# pj7.net
KiCad netlist of a schematic drawn in EAGLE
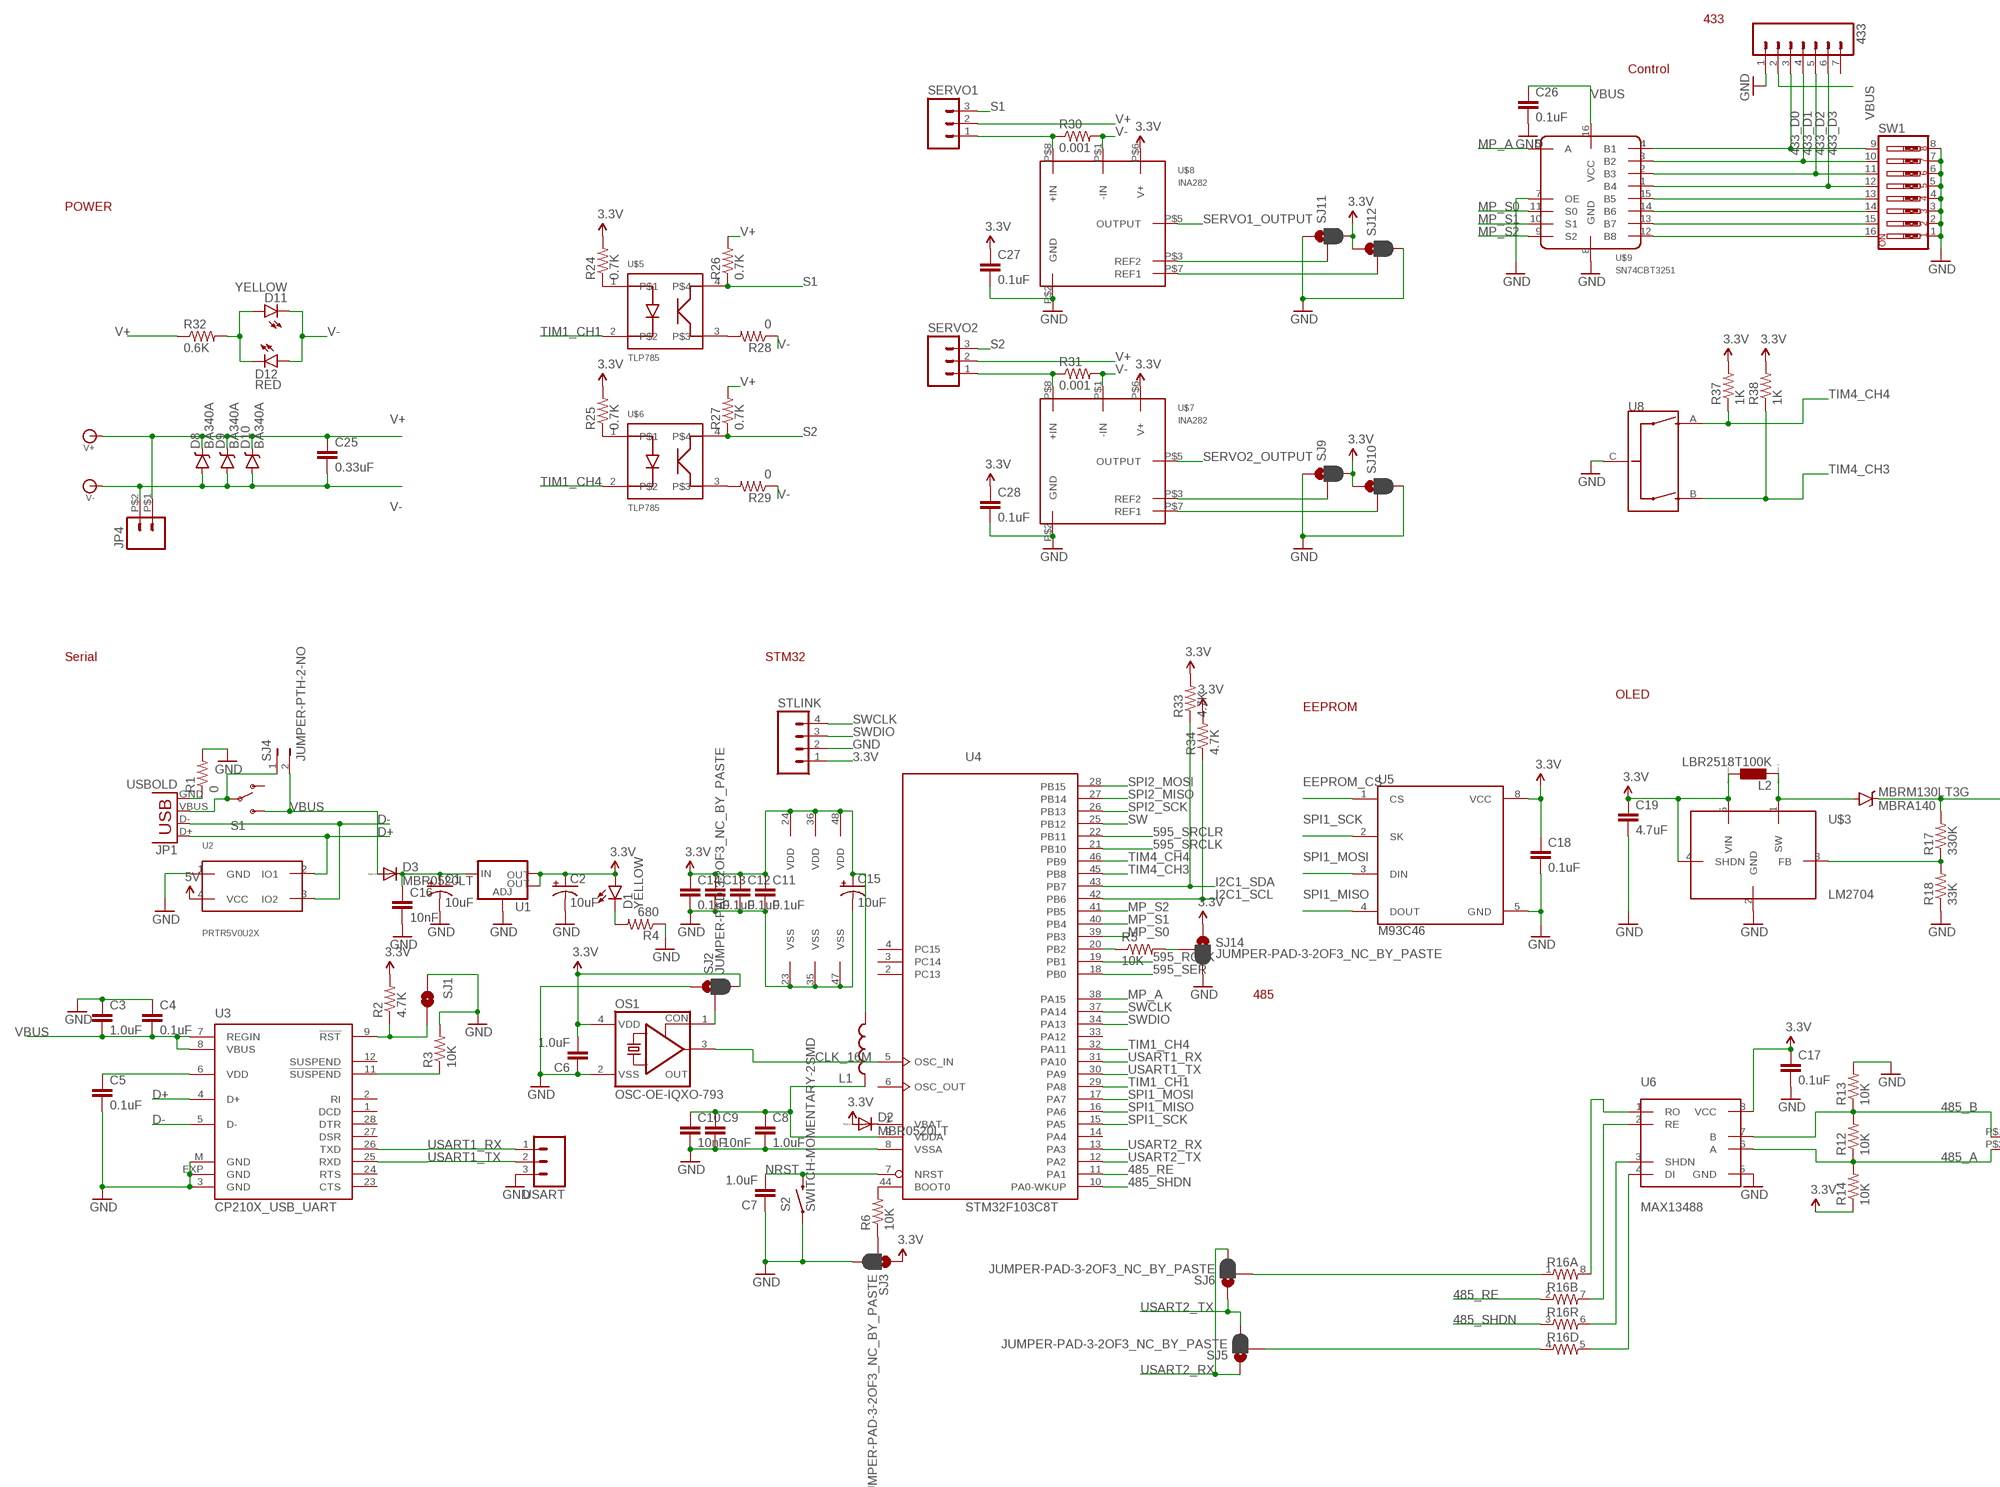
[diagram p0: schematic, sheet 1, part 1 of 2]
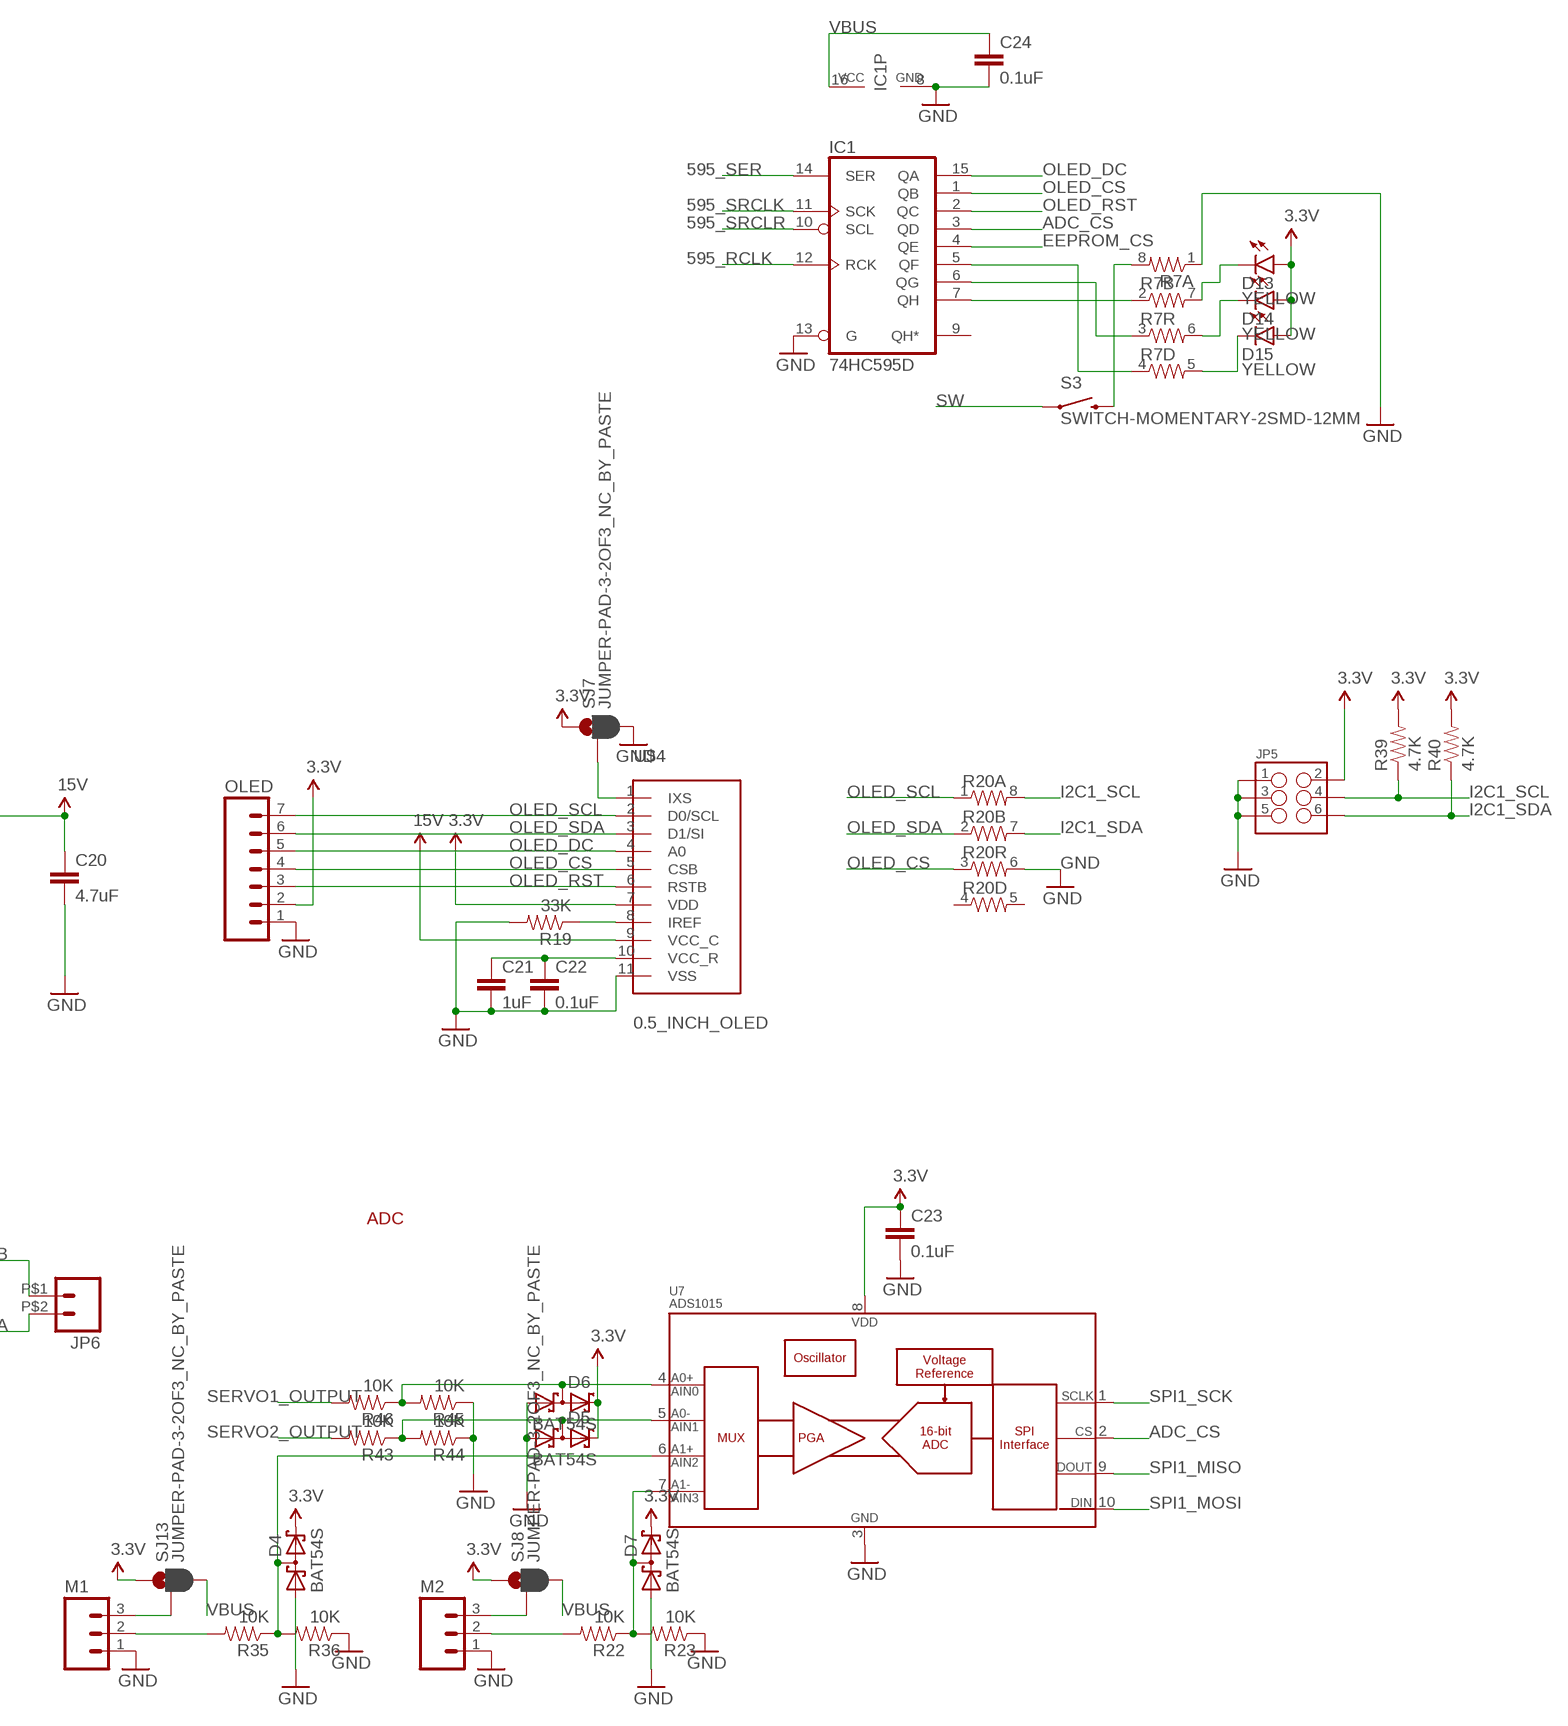
[diagram p1: schematic, sheet 1, part 2 of 2]

(export (version "E")
  (design (tool "Eeschema 10.0.6"))
  (components
    (comp (ref "433")
      (value "M07LOCK")
      (footprint "eagle-import:1X07_LOCK")
      (libsource (lib "eagle-import") (part "M07LOCK"))
    )
    (comp (ref "C1")
      (value "10uF")
      (footprint "eagle-import:EIA3216")
      (libsource (lib "eagle-import") (part "10UF-16V-10%(TANT)"))
    )
    (comp (ref "C2")
      (value "10uF")
      (footprint "eagle-import:EIA3216")
      (libsource (lib "eagle-import") (part "10UF-16V-10%(TANT)"))
    )
    (comp (ref "C3")
      (value "1.0uF")
      (footprint "eagle-import:0603-CAP")
      (libsource (lib "eagle-import") (part "1.0UF-16V-10%(0603)"))
    )
    (comp (ref "C4")
      (value "0.1uF")
      (footprint "eagle-import:0603-CAP")
      (libsource (lib "eagle-import") (part "0.1UF-25V-5%(0603)"))
    )
    (comp (ref "C5")
      (value "0.1uF")
      (footprint "eagle-import:0603-CAP")
      (libsource (lib "eagle-import") (part "0.1UF-25V-5%(0603)"))
    )
    (comp (ref "C6")
      (value "1.0uF")
      (footprint "eagle-import:0603-CAP")
      (libsource (lib "eagle-import") (part "1.0UF-16V-10%(0603)"))
    )
    (comp (ref "C7")
      (value "1.0uF")
      (footprint "eagle-import:0603-CAP")
      (libsource (lib "eagle-import") (part "1.0UF-16V-10%(0603)"))
    )
    (comp (ref "C8")
      (value "1.0uF")
      (footprint "eagle-import:0603-CAP")
      (libsource (lib "eagle-import") (part "1.0UF-16V-10%(0603)"))
    )
    (comp (ref "C9")
      (value "10nF")
      (footprint "eagle-import:0603-CAP")
      (libsource (lib "eagle-import") (part "10NF/10000PF-50V-10%(0603)"))
    )
    (comp (ref "C10")
      (value "10nF")
      (footprint "eagle-import:0603-CAP")
      (libsource (lib "eagle-import") (part "10NF/10000PF-50V-10%(0603)"))
    )
    (comp (ref "C11")
      (value "0.1uF")
      (footprint "eagle-import:0603-CAP")
      (libsource (lib "eagle-import") (part "0.1UF-25V-5%(0603)"))
    )
    (comp (ref "C12")
      (value "0.1uF")
      (footprint "eagle-import:0603-CAP")
      (libsource (lib "eagle-import") (part "0.1UF-25V-5%(0603)"))
    )
    (comp (ref "C13")
      (value "0.1uF")
      (footprint "eagle-import:0603-CAP")
      (libsource (lib "eagle-import") (part "0.1UF-25V-5%(0603)"))
    )
    (comp (ref "C14")
      (value "0.1uF")
      (footprint "eagle-import:0603-CAP")
      (libsource (lib "eagle-import") (part "0.1UF-25V-5%(0603)"))
    )
    (comp (ref "C15")
      (value "10uF")
      (footprint "eagle-import:EIA3216")
      (libsource (lib "eagle-import") (part "10UF-16V-10%(TANT)"))
    )
    (comp (ref "C16")
      (value "10nF")
      (footprint "eagle-import:0603-CAP")
      (libsource (lib "eagle-import") (part "10NF/10000PF-50V-10%(0603)"))
    )
    (comp (ref "C17")
      (value "0.1uF")
      (footprint "eagle-import:0603-CAP")
      (libsource (lib "eagle-import") (part "0.1UF-25V-5%(0603)"))
    )
    (comp (ref "C18")
      (value "0.1uF")
      (footprint "eagle-import:0603-CAP")
      (libsource (lib "eagle-import") (part "0.1UF-25V-5%(0603)"))
    )
    (comp (ref "C19")
      (value "4.7uF")
      (footprint "eagle-import:0603-CAP")
      (libsource (lib "eagle-import") (part "0.1UF-25V-5%(0603)"))
    )
    (comp (ref "C20")
      (value "4.7uF")
      (footprint "eagle-import:0603-CAP")
      (libsource (lib "eagle-import") (part "0.1UF-25V-5%(0603)"))
    )
    (comp (ref "C21")
      (value "1uF")
      (footprint "eagle-import:0603-CAP")
      (libsource (lib "eagle-import") (part "0.1UF-25V-5%(0603)"))
    )
    (comp (ref "C22")
      (value "0.1uF")
      (footprint "eagle-import:0603-CAP")
      (libsource (lib "eagle-import") (part "0.1UF-25V-5%(0603)"))
    )
    (comp (ref "C23")
      (value "0.1uF")
      (footprint "eagle-import:0603-CAP")
      (libsource (lib "eagle-import") (part "0.1UF-25V-5%(0603)"))
    )
    (comp (ref "C24")
      (value "0.1uF")
      (footprint "eagle-import:0603-CAP")
      (libsource (lib "eagle-import") (part "0.1UF-25V-5%(0603)"))
    )
    (comp (ref "C25")
      (value "0.33uF")
      (footprint "eagle-import:0805-CAP")
      (libsource (lib "eagle-import") (part "0.33UF-50V-10%(0805)"))
    )
    (comp (ref "C26")
      (value "0.1uF")
      (footprint "eagle-import:0603-CAP")
      (libsource (lib "eagle-import") (part "0.1UF-25V-5%(0603)"))
    )
    (comp (ref "C27")
      (value "0.1uF")
      (footprint "eagle-import:0603-CAP")
      (libsource (lib "eagle-import") (part "0.1UF-25V-5%(0603)"))
    )
    (comp (ref "C28")
      (value "0.1uF")
      (footprint "eagle-import:0603-CAP")
      (libsource (lib "eagle-import") (part "0.1UF-25V-5%(0603)"))
    )
    (comp (ref "D1")
      (value "YELLOW")
      (footprint "eagle-import:LED-1206")
      (libsource (lib "eagle-import") (part "LED-YELLOW1206"))
    )
    (comp (ref "D2")
      (value "MBR0520LT")
      (footprint "eagle-import:SOD123")
      (libsource (lib "eagle-import") (part "MBR0520LT"))
    )
    (comp (ref "D3")
      (value "MBR0520LT")
      (footprint "eagle-import:SOD123")
      (libsource (lib "eagle-import") (part "MBR0520LT"))
    )
    (comp (ref "D4")
      (value "BAT54S")
      (footprint "eagle-import:SOT23")
      (libsource (lib "eagle-import") (part "BAT54S"))
    )
    (comp (ref "D5")
      (value "BAT54S")
      (footprint "eagle-import:SOT23")
      (libsource (lib "eagle-import") (part "BAT54S"))
    )
    (comp (ref "D6")
      (value "BAT54S")
      (footprint "eagle-import:SOT23")
      (libsource (lib "eagle-import") (part "BAT54S"))
    )
    (comp (ref "D7")
      (value "BAT54S")
      (footprint "eagle-import:SOT23")
      (libsource (lib "eagle-import") (part "BAT54S"))
    )
    (comp (ref "D8")
      (value "BA340A")
      (footprint "eagle-import:SMA-DIODE")
      (libsource (lib "eagle-import") (part "B340A"))
    )
    (comp (ref "D9")
      (value "BA340A")
      (footprint "eagle-import:SMA-DIODE")
      (libsource (lib "eagle-import") (part "B340A"))
    )
    (comp (ref "D10")
      (value "BA340A")
      (footprint "eagle-import:SMA-DIODE")
      (libsource (lib "eagle-import") (part "B340A"))
    )
    (comp (ref "D11")
      (value "YELLOW")
      (footprint "eagle-import:LED-1206")
      (libsource (lib "eagle-import") (part "LED-YELLOW1206"))
    )
    (comp (ref "D12")
      (value "RED")
      (footprint "eagle-import:LED-1206")
      (libsource (lib "eagle-import") (part "LED-RED1206"))
    )
    (comp (ref "D13")
      (value "YELLOW")
      (footprint "eagle-import:LED-1206")
      (libsource (lib "eagle-import") (part "LED-YELLOW1206"))
    )
    (comp (ref "D14")
      (value "YELLOW")
      (footprint "eagle-import:LED-1206")
      (libsource (lib "eagle-import") (part "LED-YELLOW1206"))
    )
    (comp (ref "D15")
      (value "YELLOW")
      (footprint "eagle-import:LED-1206")
      (libsource (lib "eagle-import") (part "LED-YELLOW1206"))
    )
    (comp (ref "IC1")
      (value "74HC595D")
      (footprint "eagle-import:SO16")
      (libsource (lib "eagle-import") (part "74595DHC"))
    )
    (comp (ref "JP1")
      (value "USBOLD")
      (footprint "eagle-import:USB-MINIB-OLD")
      (libsource (lib "eagle-import") (part "USBOLD"))
    )
    (comp (ref "JP4")
      (value "M02")
      (footprint "eagle-import:1X02_5.08")
      (libsource (lib "eagle-import") (part "M02"))
    )
    (comp (ref "JP5")
      (value "M03X2")
      (footprint "eagle-import:2X3_SMD")
      (libsource (lib "eagle-import") (part "M03X2"))
    )
    (comp (ref "JP6")
      (value "M02")
      (footprint "eagle-import:1X02_5.08")
      (libsource (lib "eagle-import") (part "M02"))
    )
    (comp (ref "L1")
      (value "INDUCTOR0603")
      (footprint "eagle-import:0603")
      (libsource (lib "eagle-import") (part "INDUCTOR0603"))
    )
    (comp (ref "L2")
      (value "LBR2518T100K")
      (footprint "eagle-import:L3225P")
      (libsource (lib "eagle-import") (part "LL3225P"))
    )
    (comp (ref "M1")
      (value "M03LOCK")
      (footprint "eagle-import:1X03_LOCK")
      (libsource (lib "eagle-import") (part "M03LOCK"))
    )
    (comp (ref "M2")
      (value "M03LOCK")
      (footprint "eagle-import:1X03_LOCK")
      (libsource (lib "eagle-import") (part "M03LOCK"))
    )
    (comp (ref "MBRM130LT3G")
      (value "MBRA140")
      (footprint "eagle-import:SMA-DIODE")
      (libsource (lib "eagle-import") (part "MBRA140"))
    )
    (comp (ref "OLED")
      (value "M07LOCK")
      (footprint "eagle-import:1X07_LOCK")
      (libsource (lib "eagle-import") (part "M07LOCK"))
    )
    (comp (ref "OS1")
      (value "OSC-OE-IQXO-793")
      (footprint "eagle-import:2.5X2-4-PAD")
      (libsource (lib "eagle-import") (part "OSC-OE-IQXO-793"))
    )
    (comp (ref "R1")
      (value "0")
      (footprint "eagle-import:0603")
      (libsource (lib "eagle-import") (part "0OHM-1/10W-5%(0603)"))
    )
    (comp (ref "R2")
      (value "4.7K")
      (footprint "eagle-import:0603-RES")
      (libsource (lib "eagle-import") (part "4.7KOHM-1/10W-1%(0603)"))
    )
    (comp (ref "R3")
      (value "10K")
      (footprint "eagle-import:0603-RES")
      (libsource (lib "eagle-import") (part "4.7KOHM-1/10W-1%(0603)"))
    )
    (comp (ref "R4")
      (value "680")
      (footprint "eagle-import:0603-RES")
      (libsource (lib "eagle-import") (part "680OHM1/10W5%(0603)"))
    )
    (comp (ref "R5")
      (value "10K")
      (footprint "eagle-import:0603-RES")
      (libsource (lib "eagle-import") (part "10KOHM-1/10W-1%(0603)0603"))
    )
    (comp (ref "R6")
      (value "10K")
      (footprint "eagle-import:0603-RES")
      (libsource (lib "eagle-import") (part "10KOHM-1/10W-1%(0603)0603"))
    )
    (comp (ref "R7")
      (value "RESISTOR-ARRAY0603-ARV")
      (footprint "eagle-import:0603-ARV")
      (libsource (lib "eagle-import") (part "RESISTOR-ARRAY0603-ARV"))
    )
    (comp (ref "R12")
      (value "10K")
      (footprint "eagle-import:0603-RES")
      (libsource (lib "eagle-import") (part "10KOHM-1/10W-1%(0603)0603"))
    )
    (comp (ref "R13")
      (value "10K")
      (footprint "eagle-import:0603-RES")
      (libsource (lib "eagle-import") (part "10KOHM-1/10W-1%(0603)0603"))
    )
    (comp (ref "R14")
      (value "10K")
      (footprint "eagle-import:0603-RES")
      (libsource (lib "eagle-import") (part "10KOHM-1/10W-1%(0603)0603"))
    )
    (comp (ref "R16")
      (value "RESISTOR-ARRAY0603-ARV")
      (footprint "eagle-import:0603-ARV")
      (libsource (lib "eagle-import") (part "RESISTOR-ARRAY0603-ARV"))
    )
    (comp (ref "R17")
      (value "330K")
      (footprint "eagle-import:0603-RES")
      (libsource (lib "eagle-import") (part "10KOHM-1/10W-1%(0603)0603"))
    )
    (comp (ref "R18")
      (value "33K")
      (footprint "eagle-import:0603-RES")
      (libsource (lib "eagle-import") (part "10KOHM-1/10W-1%(0603)0603"))
    )
    (comp (ref "R19")
      (value "33K")
      (footprint "eagle-import:0603-RES")
      (libsource (lib "eagle-import") (part "10KOHM-1/10W-1%(0603)0603"))
    )
    (comp (ref "R20")
      (value "RESISTOR-ARRAY0603-ARV")
      (footprint "eagle-import:0603-ARV")
      (libsource (lib "eagle-import") (part "RESISTOR-ARRAY0603-ARV"))
    )
    (comp (ref "R22")
      (value "10K")
      (footprint "eagle-import:0603-RES")
      (libsource (lib "eagle-import") (part "10KOHM-1/10W-1%(0603)0603"))
    )
    (comp (ref "R23")
      (value "10K")
      (footprint "eagle-import:0603-RES")
      (libsource (lib "eagle-import") (part "10KOHM-1/10W-1%(0603)0603"))
    )
    (comp (ref "R24")
      (value "0.7K")
      (footprint "eagle-import:0603")
      (libsource (lib "eagle-import") (part "0OHM-1/10W-5%(0603)"))
    )
    (comp (ref "R25")
      (value "0.7K")
      (footprint "eagle-import:0603")
      (libsource (lib "eagle-import") (part "0OHM-1/10W-5%(0603)"))
    )
    (comp (ref "R26")
      (value "0.7K")
      (footprint "eagle-import:0603")
      (libsource (lib "eagle-import") (part "0OHM-1/10W-5%(0603)"))
    )
    (comp (ref "R27")
      (value "0.7K")
      (footprint "eagle-import:0603")
      (libsource (lib "eagle-import") (part "0OHM-1/10W-5%(0603)"))
    )
    (comp (ref "R28")
      (value "0")
      (footprint "eagle-import:0603")
      (libsource (lib "eagle-import") (part "0OHM-1/10W-5%(0603)"))
    )
    (comp (ref "R29")
      (value "0")
      (footprint "eagle-import:0603")
      (libsource (lib "eagle-import") (part "0OHM-1/10W-5%(0603)"))
    )
    (comp (ref "R30")
      (value "0.001")
      (footprint "eagle-import:2512")
      (libsource (lib "eagle-import") (part "0.001OHM-3W-1%(2512)3W/1%"))
    )
    (comp (ref "R31")
      (value "0.001")
      (footprint "eagle-import:2512")
      (libsource (lib "eagle-import") (part "0.001OHM-3W-1%(2512)3W/1%"))
    )
    (comp (ref "R32")
      (value "0.6K")
      (footprint "eagle-import:0805")
      (libsource (lib "eagle-import") (part "0.75OHM-1/4W-1%(0805)"))
    )
    (comp (ref "R33")
      (value "4.7K")
      (footprint "eagle-import:0603-RES")
      (libsource (lib "eagle-import") (part "10KOHM-1/10W-1%(0603)0603"))
    )
    (comp (ref "R34")
      (value "4.7K")
      (footprint "eagle-import:0603-RES")
      (libsource (lib "eagle-import") (part "10KOHM-1/10W-1%(0603)0603"))
    )
    (comp (ref "R35")
      (value "10K")
      (footprint "eagle-import:0603-RES")
      (libsource (lib "eagle-import") (part "10KOHM-1/10W-1%(0603)0603"))
    )
    (comp (ref "R36")
      (value "10K")
      (footprint "eagle-import:0603-RES")
      (libsource (lib "eagle-import") (part "10KOHM-1/10W-1%(0603)0603"))
    )
    (comp (ref "R37")
      (value "1K")
      (footprint "eagle-import:0603-RES")
      (libsource (lib "eagle-import") (part "10KOHM-1/10W-1%(0603)0603"))
    )
    (comp (ref "R38")
      (value "1K")
      (footprint "eagle-import:0603-RES")
      (libsource (lib "eagle-import") (part "10KOHM-1/10W-1%(0603)0603"))
    )
    (comp (ref "R39")
      (value "4.7K")
      (footprint "eagle-import:0603-RES")
      (libsource (lib "eagle-import") (part "10KOHM-1/10W-1%(0603)0603"))
    )
    (comp (ref "R40")
      (value "4.7K")
      (footprint "eagle-import:0603-RES")
      (libsource (lib "eagle-import") (part "10KOHM-1/10W-1%(0603)0603"))
    )
    (comp (ref "R43")
      (value "10K")
      (footprint "eagle-import:0603-RES")
      (libsource (lib "eagle-import") (part "10KOHM-1/10W-1%(0603)0603"))
    )
    (comp (ref "R44")
      (value "10K")
      (footprint "eagle-import:0603-RES")
      (libsource (lib "eagle-import") (part "10KOHM-1/10W-1%(0603)0603"))
    )
    (comp (ref "R45")
      (value "10K")
      (footprint "eagle-import:0603-RES")
      (libsource (lib "eagle-import") (part "10KOHM-1/10W-1%(0603)0603"))
    )
    (comp (ref "R46")
      (value "10K")
      (footprint "eagle-import:0603-RES")
      (libsource (lib "eagle-import") (part "10KOHM-1/10W-1%(0603)0603"))
    )
    (comp (ref "S1")
      (value "SWITCH-SPDTSMD")
      (footprint "eagle-import:AYZ0202")
      (libsource (lib "eagle-import") (part "SWITCH-SPDTSMD"))
    )
    (comp (ref "S2")
      (value "SWITCH-MOMENTARY-2SMD")
      (footprint "eagle-import:TACTILE-SWITCH-SMD")
      (libsource (lib "eagle-import") (part "SWITCH-MOMENTARY-2SMD"))
    )
    (comp (ref "S3")
      (value "SWITCH-MOMENTARY-2SMD-12MM")
      (footprint "eagle-import:TACTILE-SMD-12MM")
      (libsource (lib "eagle-import") (part "SWITCH-MOMENTARY-2SMD-12MM"))
    )
    (comp (ref "SERVO1")
      (value "M03LOCK_LONGPADS")
      (footprint "eagle-import:1X03_LOCK_LONGPADS")
      (libsource (lib "eagle-import") (part "M03LOCK_LONGPADS"))
    )
    (comp (ref "SERVO2")
      (value "M03LOCK_LONGPADS")
      (footprint "eagle-import:1X03_LOCK_LONGPADS")
      (libsource (lib "eagle-import") (part "M03LOCK_LONGPADS"))
    )
    (comp (ref "SJ1")
      (value "JUMPER-PAD-2-NOYES_SILK")
      (footprint "eagle-import:PAD-JUMPER-2-NO_YES_SILK")
      (libsource (lib "eagle-import") (part "JUMPER-PAD-2-NOYES_SILK"))
    )
    (comp (ref "SJ2")
      (value "JUMPER-PAD-3-2OF3_NC_BY_PASTE")
      (footprint "eagle-import:PAD-JUMPER-3-2OF3_NC_BY_PASTE_YES_SILK_FULL_BOX")
      (libsource (lib "eagle-import") (part "JUMPER-PAD-3-2OF3_NC_BY_PASTE"))
    )
    (comp (ref "SJ3")
      (value "JUMPER-PAD-3-2OF3_NC_BY_PASTE")
      (footprint "eagle-import:PAD-JUMPER-3-2OF3_NC_BY_PASTE_YES_SILK_FULL_BOX")
      (libsource (lib "eagle-import") (part "JUMPER-PAD-3-2OF3_NC_BY_PASTE"))
    )
    (comp (ref "SJ4")
      (value "JUMPER-PTH-2-NO")
      (footprint "eagle-import:PTH-JUMPER-2-NO_NO_SILK")
      (libsource (lib "eagle-import") (part "JUMPER-PTH-2-NO"))
    )
    (comp (ref "SJ5")
      (value "JUMPER-PAD-3-2OF3_NC_BY_PASTE")
      (footprint "eagle-import:PAD-JUMPER-3-2OF3_NC_BY_PASTE_YES_SILK_FULL_BOX")
      (libsource (lib "eagle-import") (part "JUMPER-PAD-3-2OF3_NC_BY_PASTE"))
    )
    (comp (ref "SJ6")
      (value "JUMPER-PAD-3-2OF3_NC_BY_PASTE")
      (footprint "eagle-import:PAD-JUMPER-3-2OF3_NC_BY_PASTE_YES_SILK_FULL_BOX")
      (libsource (lib "eagle-import") (part "JUMPER-PAD-3-2OF3_NC_BY_PASTE"))
    )
    (comp (ref "SJ7")
      (value "JUMPER-PAD-3-2OF3_NC_BY_PASTE")
      (footprint "eagle-import:PAD-JUMPER-3-2OF3_NC_BY_PASTE_YES_SILK_FULL_BOX")
      (libsource (lib "eagle-import") (part "JUMPER-PAD-3-2OF3_NC_BY_PASTE"))
    )
    (comp (ref "SJ8")
      (value "JUMPER-PAD-3-2OF3_NC_BY_PASTE")
      (footprint "eagle-import:PAD-JUMPER-3-2OF3_NC_BY_PASTE_YES_SILK_FULL_BOX")
      (libsource (lib "eagle-import") (part "JUMPER-PAD-3-2OF3_NC_BY_PASTE"))
    )
    (comp (ref "SJ9")
      (value "JUMPER-PAD-3-2OF3_NC_BY_PASTE")
      (footprint "eagle-import:PAD-JUMPER-3-2OF3_NC_BY_PASTE_YES_SILK_FULL_BOX")
      (libsource (lib "eagle-import") (part "JUMPER-PAD-3-2OF3_NC_BY_PASTE"))
    )
    (comp (ref "SJ10")
      (value "JUMPER-PAD-3-2OF3_NC_BY_PASTE")
      (footprint "eagle-import:PAD-JUMPER-3-2OF3_NC_BY_PASTE_YES_SILK_FULL_BOX")
      (libsource (lib "eagle-import") (part "JUMPER-PAD-3-2OF3_NC_BY_PASTE"))
    )
    (comp (ref "SJ11")
      (value "JUMPER-PAD-3-2OF3_NC_BY_PASTE")
      (footprint "eagle-import:PAD-JUMPER-3-2OF3_NC_BY_PASTE_YES_SILK_FULL_BOX")
      (libsource (lib "eagle-import") (part "JUMPER-PAD-3-2OF3_NC_BY_PASTE"))
    )
    (comp (ref "SJ12")
      (value "JUMPER-PAD-3-2OF3_NC_BY_PASTE")
      (footprint "eagle-import:PAD-JUMPER-3-2OF3_NC_BY_PASTE_YES_SILK_FULL_BOX")
      (libsource (lib "eagle-import") (part "JUMPER-PAD-3-2OF3_NC_BY_PASTE"))
    )
    (comp (ref "SJ13")
      (value "JUMPER-PAD-3-2OF3_NC_BY_PASTE")
      (footprint "eagle-import:PAD-JUMPER-3-2OF3_NC_BY_PASTE_YES_SILK_FULL_BOX")
      (libsource (lib "eagle-import") (part "JUMPER-PAD-3-2OF3_NC_BY_PASTE"))
    )
    (comp (ref "SJ14")
      (value "JUMPER-PAD-3-2OF3_NC_BY_PASTE")
      (footprint "eagle-import:PAD-JUMPER-3-2OF3_NC_BY_PASTE_YES_SILK_FULL_BOX")
      (libsource (lib "eagle-import") (part "JUMPER-PAD-3-2OF3_NC_BY_PASTE"))
    )
    (comp (ref "STLINK")
      (value "M04LOCK")
      (footprint "eagle-import:1X04_LOCK")
      (libsource (lib "eagle-import") (part "M04LOCK"))
    )
    (comp (ref "SW1")
      (value "SW_DIP-8-SMT-HALFSIZE")
      (footprint "eagle-import:DIPSWITCH-08-50MIL")
      (libsource (lib "eagle-import") (part "SW_DIP-8-SMT-HALFSIZE"))
    )
    (comp (ref "U$3")
      (value "LM2704")
      (footprint "eagle-import:SOT23-5")
      (libsource (lib "eagle-import") (part "LM2704"))
    )
    (comp (ref "U$4")
      (value "0.5_INCH_OLED")
      (footprint "eagle-import:BL125-11RL-TAGF")
      (libsource (lib "eagle-import") (part "0.5_INCH_OLED"))
    )
    (comp (ref "U$5")
      (value "TLP785")
      (footprint "eagle-import:DIL04")
      (libsource (lib "eagle-import") (part "TLP785"))
    )
    (comp (ref "U$6")
      (value "TLP785")
      (footprint "eagle-import:DIL04")
      (libsource (lib "eagle-import") (part "TLP785"))
    )
    (comp (ref "U$7")
      (value "INA282")
      (footprint "eagle-import:SOP8")
      (libsource (lib "eagle-import") (part "INA282"))
    )
    (comp (ref "U$8")
      (value "INA282")
      (footprint "eagle-import:SOP8")
      (libsource (lib "eagle-import") (part "INA282"))
    )
    (comp (ref "U$9")
      (value "SN74CBT3251")
      (footprint "eagle-import:TSSOP16")
      (libsource (lib "eagle-import") (part "SN74CBT3251"))
    )
    (comp (ref "U1")
      (value "V_REG_LM1117SOT223")
      (footprint "eagle-import:SOT223")
      (libsource (lib "eagle-import") (part "V_REG_LM1117SOT223"))
    )
    (comp (ref "U2")
      (value "PRTR5V0U2X")
      (footprint "eagle-import:SOT143")
      (libsource (lib "eagle-import") (part "PRTR5V0U2X"))
    )
    (comp (ref "U3")
      (value "CP210X_USB_UART")
      (footprint "eagle-import:MLP28")
      (libsource (lib "eagle-import") (part "CP210X_USB_UART"))
    )
    (comp (ref "U4")
      (value "STM32F103C8T")
      (footprint "eagle-import:LQFP48")
      (libsource (lib "eagle-import") (part "STM32F103CT8"))
    )
    (comp (ref "U5")
      (value "M93C46")
      (footprint "eagle-import:SO08")
      (libsource (lib "eagle-import") (part "M93C46"))
    )
    (comp (ref "U6")
      (value "MAX13488")
      (footprint "eagle-import:SOIC8")
      (libsource (lib "eagle-import") (part "MAX13488"))
    )
    (comp (ref "U7")
      (value "ADS1015")
      (footprint "eagle-import:MSOP10")
      (libsource (lib "eagle-import") (part "ADS1118"))
    )
    (comp (ref "U8")
      (value "ENCODER-QUADRATURE")
      (footprint "eagle-import:ENCODER-16MM-QUAD")
      (libsource (lib "eagle-import") (part "ENCODER-QUADRATURE"))
    )
    (comp (ref "USART")
      (value "M03LOCK")
      (footprint "eagle-import:1X03_LOCK")
      (libsource (lib "eagle-import") (part "M03LOCK"))
    )
    (comp (ref "V+")
      (value "BANANA_CONN")
      (footprint "eagle-import:BANANA_CONN")
      (libsource (lib "eagle-import") (part "BANANA_CONN"))
    )
    (comp (ref "V-")
      (value "BANANA_CONN")
      (footprint "eagle-import:BANANA_CONN")
      (libsource (lib "eagle-import") (part "BANANA_CONN"))
    )
  )
  (nets
    (net (code "1") (name "/433_D0") (class "Default")
      (node (ref "433") (pin "3") (pinfunction "3_3") (pintype "passive"))
      (node (ref "SW1") (pin "9") (pinfunction "9_9") (pintype "passive"))
      (node (ref "U$9") (pin "4") (pinfunction "B1_4") (pintype "bidirectional"))
    )
    (net (code "2") (name "/433_D1") (class "Default")
      (node (ref "433") (pin "4") (pinfunction "4_4") (pintype "passive"))
      (node (ref "SW1") (pin "10") (pinfunction "10_10") (pintype "passive"))
      (node (ref "U$9") (pin "3") (pinfunction "B2_3") (pintype "bidirectional"))
    )
    (net (code "3") (name "/433_D2") (class "Default")
      (node (ref "433") (pin "5") (pinfunction "5_5") (pintype "passive"))
      (node (ref "SW1") (pin "11") (pinfunction "11_11") (pintype "passive"))
      (node (ref "U$9") (pin "2") (pinfunction "B3_2") (pintype "bidirectional"))
    )
    (net (code "4") (name "/433_D3") (class "Default")
      (node (ref "433") (pin "6") (pinfunction "6_6") (pintype "passive"))
      (node (ref "SW1") (pin "12") (pinfunction "12_12") (pintype "passive"))
      (node (ref "U$9") (pin "1") (pinfunction "B4_1") (pintype "bidirectional"))
    )
    (net (code "5") (name "/485_A") (class "Default")
      (node (ref "JP6") (pin "P$2") (pinfunction "2_P$2") (pintype "passive"))
      (node (ref "R12") (pin "1") (pinfunction "1_1") (pintype "passive"))
      (node (ref "R14") (pin "2") (pinfunction "2_2") (pintype "passive"))
      (node (ref "U6") (pin "6") (pinfunction "A_6") (pintype "bidirectional"))
    )
    (net (code "6") (name "/485_B") (class "Default")
      (node (ref "JP6") (pin "P$1") (pinfunction "1_P$1") (pintype "passive"))
      (node (ref "R12") (pin "2") (pinfunction "2_2") (pintype "passive"))
      (node (ref "R13") (pin "1") (pinfunction "1_1") (pintype "passive"))
      (node (ref "U6") (pin "7") (pinfunction "B_7") (pintype "bidirectional"))
    )
    (net (code "7") (name "/485_RE") (class "Default")
      (node (ref "R16") (pin "2") (pinfunction "1_2") (pintype "passive"))
      (node (ref "U4") (pin "11") (pinfunction "PA1_11") (pintype "bidirectional"))
    )
    (net (code "8") (name "/485_SHDN") (class "Default")
      (node (ref "R16") (pin "3") (pinfunction "1_3") (pintype "passive"))
      (node (ref "U4") (pin "10") (pinfunction "PA0-WKUP_10") (pintype "bidirectional"))
    )
    (net (code "9") (name "/595_RCLK") (class "Default")
      (node (ref "IC1") (pin "12") (pinfunction "RCK_12") (pintype "input"))
      (node (ref "U4") (pin "19") (pinfunction "PB1_19") (pintype "bidirectional"))
    )
    (net (code "10") (name "/595_SER") (class "Default")
      (node (ref "IC1") (pin "14") (pinfunction "SER_14") (pintype "input"))
      (node (ref "U4") (pin "18") (pinfunction "PB0_18") (pintype "bidirectional"))
    )
    (net (code "11") (name "/595_SRCLK") (class "Default")
      (node (ref "IC1") (pin "11") (pinfunction "SCK_11") (pintype "input"))
      (node (ref "U4") (pin "21") (pinfunction "PB10_21") (pintype "bidirectional"))
    )
    (net (code "12") (name "/595_SRCLR") (class "Default")
      (node (ref "IC1") (pin "10") (pinfunction "SCL_10") (pintype "input"))
      (node (ref "U4") (pin "22") (pinfunction "PB11_22") (pintype "bidirectional"))
    )
    (net (code "13") (name "/ADC_CS") (class "Default")
      (node (ref "IC1") (pin "3") (pinfunction "QD_3") (pintype "tri_state"))
      (node (ref "U7") (pin "2") (pinfunction "CS_2") (pintype "bidirectional"))
    )
    (net (code "14") (name "/CLK_16M") (class "Default")
      (node (ref "OS1") (pin "3") (pinfunction "OUT_3") (pintype "output"))
      (node (ref "U4") (pin "5") (pinfunction "OSC_IN_5") (pintype "bidirectional"))
    )
    (net (code "15") (name "/D+") (class "Default")
      (node (ref "JP1") (pin "D+") (pinfunction "D+_D+") (pintype "bidirectional"))
      (node (ref "U2") (pin "2") (pinfunction "IO1_2") (pintype "bidirectional"))
      (node (ref "U3") (pin "4") (pinfunction "D+_4") (pintype "bidirectional"))
    )
    (net (code "16") (name "/D-") (class "Default")
      (node (ref "JP1") (pin "D-") (pinfunction "D-_D-") (pintype "bidirectional"))
      (node (ref "U2") (pin "3") (pinfunction "IO2_3") (pintype "bidirectional"))
      (node (ref "U3") (pin "5") (pinfunction "D-_5") (pintype "bidirectional"))
    )
    (net (code "17") (name "/EEPROM_CS") (class "Default")
      (node (ref "IC1") (pin "4") (pinfunction "QE_4") (pintype "tri_state"))
      (node (ref "U5") (pin "1") (pinfunction "CS_1") (pintype "bidirectional"))
    )
    (net (code "18") (name "/I2C1_SCL") (class "Default")
      (node (ref "JP5") (pin "4") (pinfunction "4_4") (pintype "bidirectional"))
      (node (ref "R20") (pin "8") (pinfunction "2_8") (pintype "passive"))
      (node (ref "R34") (pin "1") (pinfunction "1_1") (pintype "passive"))
      (node (ref "R39") (pin "1") (pinfunction "1_1") (pintype "passive"))
      (node (ref "U4") (pin "42") (pinfunction "PB6_42") (pintype "bidirectional"))
    )
    (net (code "19") (name "/I2C1_SDA") (class "Default")
      (node (ref "JP5") (pin "6") (pinfunction "6_6") (pintype "bidirectional"))
      (node (ref "R20") (pin "7") (pinfunction "2_7") (pintype "passive"))
      (node (ref "R33") (pin "1") (pinfunction "1_1") (pintype "passive"))
      (node (ref "R40") (pin "1") (pinfunction "1_1") (pintype "passive"))
      (node (ref "U4") (pin "43") (pinfunction "PB7_43") (pintype "bidirectional"))
    )
    (net (code "20") (name "/MP_A") (class "Default")
      (node (ref "U$9") (pin "5") (pinfunction "A_5") (pintype "bidirectional"))
      (node (ref "U4") (pin "38") (pinfunction "PA15_38") (pintype "bidirectional"))
    )
    (net (code "21") (name "/MP_S0") (class "Default")
      (node (ref "U$9") (pin "11") (pinfunction "S0_11") (pintype "bidirectional"))
      (node (ref "U4") (pin "39") (pinfunction "PB3_39") (pintype "bidirectional"))
    )
    (net (code "22") (name "/MP_S1") (class "Default")
      (node (ref "U$9") (pin "10") (pinfunction "S1_10") (pintype "bidirectional"))
      (node (ref "U4") (pin "40") (pinfunction "PB4_40") (pintype "bidirectional"))
    )
    (net (code "23") (name "/MP_S2") (class "Default")
      (node (ref "U$9") (pin "9") (pinfunction "S2_9") (pintype "bidirectional"))
      (node (ref "U4") (pin "41") (pinfunction "PB5_41") (pintype "bidirectional"))
    )
    (net (code "24") (name "/NRST") (class "Default")
      (node (ref "C7") (pin "2") (pinfunction "2_2") (pintype "passive"))
      (node (ref "S2") (pin "3") (pinfunction "2_3") (pintype "passive"))
      (node (ref "U4") (pin "7") (pinfunction "NRST_7") (pintype "bidirectional"))
    )
    (net (code "25") (name "/OLED_CS") (class "Default")
      (node (ref "IC1") (pin "1") (pinfunction "QB_1") (pintype "tri_state"))
      (node (ref "OLED") (pin "4") (pinfunction "4_4") (pintype "passive"))
      (node (ref "R20") (pin "3") (pinfunction "1_3") (pintype "passive"))
      (node (ref "U$4") (pin "5") (pinfunction "CSB_5") (pintype "bidirectional"))
    )
    (net (code "26") (name "/OLED_DC") (class "Default")
      (node (ref "IC1") (pin "15") (pinfunction "QA_15") (pintype "tri_state"))
      (node (ref "OLED") (pin "5") (pinfunction "5_5") (pintype "passive"))
      (node (ref "U$4") (pin "4") (pinfunction "A0_4") (pintype "bidirectional"))
    )
    (net (code "27") (name "/OLED_RST") (class "Default")
      (node (ref "IC1") (pin "2") (pinfunction "QC_2") (pintype "tri_state"))
      (node (ref "OLED") (pin "3") (pinfunction "3_3") (pintype "passive"))
      (node (ref "U$4") (pin "6") (pinfunction "RSTB_6") (pintype "bidirectional"))
    )
    (net (code "28") (name "/OLED_SCL") (class "Default")
      (node (ref "OLED") (pin "7") (pinfunction "7_7") (pintype "passive"))
      (node (ref "R20") (pin "1") (pinfunction "1_1") (pintype "passive"))
      (node (ref "U$4") (pin "2") (pinfunction "D0/SCL_2") (pintype "bidirectional"))
    )
    (net (code "29") (name "/OLED_SDA") (class "Default")
      (node (ref "OLED") (pin "6") (pinfunction "6_6") (pintype "passive"))
      (node (ref "R20") (pin "2") (pinfunction "1_2") (pintype "passive"))
      (node (ref "U$4") (pin "3") (pinfunction "D1/SI_3") (pintype "bidirectional"))
    )
    (net (code "30") (name "/S1") (class "Default")
      (node (ref "R26") (pin "1") (pinfunction "1_1") (pintype "passive"))
      (node (ref "SERVO1") (pin "3") (pinfunction "3_3") (pintype "passive"))
      (node (ref "U$5") (pin "4") (pinfunction "P$4_4") (pintype "bidirectional"))
    )
    (net (code "31") (name "/S2") (class "Default")
      (node (ref "R27") (pin "1") (pinfunction "1_1") (pintype "passive"))
      (node (ref "SERVO2") (pin "3") (pinfunction "3_3") (pintype "passive"))
      (node (ref "U$6") (pin "4") (pinfunction "P$4_4") (pintype "bidirectional"))
    )
    (net (code "32") (name "/SERVO1_OUTPUT") (class "Default")
      (node (ref "R46") (pin "2") (pinfunction "2_2") (pintype "passive"))
      (node (ref "U$8") (pin "P$5") (pinfunction "OUTPUT_P$5") (pintype "bidirectional"))
    )
    (net (code "33") (name "/SERVO2_OUTPUT") (class "Default")
      (node (ref "R43") (pin "2") (pinfunction "2_2") (pintype "passive"))
      (node (ref "U$7") (pin "P$5") (pinfunction "OUTPUT_P$5") (pintype "bidirectional"))
    )
    (net (code "34") (name "/SPI1_MISO") (class "Default")
      (node (ref "U4") (pin "16") (pinfunction "PA6_16") (pintype "bidirectional"))
      (node (ref "U5") (pin "4") (pinfunction "DOUT_4") (pintype "bidirectional"))
      (node (ref "U7") (pin "9") (pinfunction "DOUT/DRDY_9") (pintype "bidirectional"))
    )
    (net (code "35") (name "/SPI1_MOSI") (class "Default")
      (node (ref "U4") (pin "17") (pinfunction "PA7_17") (pintype "bidirectional"))
      (node (ref "U5") (pin "3") (pinfunction "DIN_3") (pintype "bidirectional"))
      (node (ref "U7") (pin "10") (pinfunction "DIN_10") (pintype "bidirectional"))
    )
    (net (code "36") (name "/SPI1_SCK") (class "Default")
      (node (ref "U4") (pin "15") (pinfunction "PA5_15") (pintype "bidirectional"))
      (node (ref "U5") (pin "2") (pinfunction "SK_2") (pintype "bidirectional"))
      (node (ref "U7") (pin "1") (pinfunction "SCLK_1") (pintype "bidirectional"))
    )
    (net (code "37") (name "/SPI2_MISO") (class "Default")
      (node (ref "U4") (pin "27") (pinfunction "PB14_27") (pintype "bidirectional"))
    )
    (net (code "38") (name "/SPI2_MOSI") (class "Default")
      (node (ref "U4") (pin "28") (pinfunction "PB15_28") (pintype "bidirectional"))
    )
    (net (code "39") (name "/SPI2_SCK") (class "Default")
      (node (ref "U4") (pin "26") (pinfunction "PB13_26") (pintype "bidirectional"))
    )
    (net (code "40") (name "/SW") (class "Default")
      (node (ref "S3") (pin "1") (pinfunction "1_1") (pintype "passive"))
      (node (ref "U4") (pin "25") (pinfunction "PB12_25") (pintype "bidirectional"))
    )
    (net (code "41") (name "/SWCLK") (class "Default")
      (node (ref "STLINK") (pin "4") (pinfunction "4_4") (pintype "passive"))
      (node (ref "U4") (pin "37") (pinfunction "PA14_37") (pintype "bidirectional"))
    )
    (net (code "42") (name "/SWDIO") (class "Default")
      (node (ref "STLINK") (pin "3") (pinfunction "3_3") (pintype "passive"))
      (node (ref "U4") (pin "34") (pinfunction "PA13_34") (pintype "bidirectional"))
    )
    (net (code "43") (name "/TIM1_CH1") (class "Default")
      (node (ref "U$5") (pin "2") (pinfunction "P$2_2") (pintype "bidirectional"))
      (node (ref "U4") (pin "29") (pinfunction "PA8_29") (pintype "bidirectional"))
    )
    (net (code "44") (name "/TIM1_CH4") (class "Default")
      (node (ref "U$6") (pin "2") (pinfunction "P$2_2") (pintype "bidirectional"))
      (node (ref "U4") (pin "32") (pinfunction "PA11_32") (pintype "bidirectional"))
    )
    (net (code "45") (name "/TIM4_CH3") (class "Default")
      (node (ref "R38") (pin "1") (pinfunction "1_1") (pintype "passive"))
      (node (ref "U4") (pin "45") (pinfunction "PB8_45") (pintype "bidirectional"))
      (node (ref "U8") (pin "B") (pinfunction "B_B") (pintype "bidirectional"))
    )
    (net (code "46") (name "/TIM4_CH4") (class "Default")
      (node (ref "R37") (pin "1") (pinfunction "1_1") (pintype "passive"))
      (node (ref "U4") (pin "46") (pinfunction "PB9_46") (pintype "bidirectional"))
      (node (ref "U8") (pin "A") (pinfunction "A_A") (pintype "bidirectional"))
    )
    (net (code "47") (name "/USART1_RX") (class "Default")
      (node (ref "U3") (pin "26") (pinfunction "TXD_26") (pintype "output"))
      (node (ref "U4") (pin "31") (pinfunction "PA10_31") (pintype "bidirectional"))
      (node (ref "USART") (pin "1") (pinfunction "1_1") (pintype "passive"))
    )
    (net (code "48") (name "/USART1_TX") (class "Default")
      (node (ref "U3") (pin "25") (pinfunction "RXD_25") (pintype "input"))
      (node (ref "U4") (pin "30") (pinfunction "PA9_30") (pintype "bidirectional"))
      (node (ref "USART") (pin "2") (pinfunction "2_2") (pintype "passive"))
    )
    (net (code "49") (name "/USART2_RX") (class "Default")
      (node (ref "SJ5") (pin "1") (pinfunction "1_1") (pintype "passive"))
      (node (ref "SJ6") (pin "3") (pinfunction "3_3") (pintype "passive"))
      (node (ref "U4") (pin "13") (pinfunction "PA3_13") (pintype "bidirectional"))
    )
    (net (code "50") (name "/USART2_TX") (class "Default")
      (node (ref "SJ5") (pin "3") (pinfunction "3_3") (pintype "passive"))
      (node (ref "SJ6") (pin "1") (pinfunction "1_1") (pintype "passive"))
      (node (ref "U4") (pin "12") (pinfunction "PA2_12") (pintype "bidirectional"))
    )
    (net (code "51") (name "/V+") (class "Default")
      (node (ref "C25") (pin "1") (pinfunction "1_1") (pintype "passive"))
      (node (ref "D10") (pin "C") (pinfunction "C_C") (pintype "passive"))
      (node (ref "D8") (pin "C") (pinfunction "C_C") (pintype "passive"))
      (node (ref "D9") (pin "C") (pinfunction "C_C") (pintype "passive"))
      (node (ref "JP4") (pin "P$1") (pinfunction "1_P$1") (pintype "passive"))
      (node (ref "R26") (pin "2") (pinfunction "2_2") (pintype "passive"))
      (node (ref "R27") (pin "2") (pinfunction "2_2") (pintype "passive"))
      (node (ref "R32") (pin "1") (pinfunction "1_1") (pintype "passive"))
      (node (ref "SERVO1") (pin "2") (pinfunction "2_2") (pintype "passive"))
      (node (ref "SERVO2") (pin "2") (pinfunction "2_2") (pintype "passive"))
      (node (ref "V+") (pin "P$1") (pinfunction "1_P$1") (pintype "passive"))
    )
    (net (code "52") (name "/V-") (class "Default")
      (node (ref "C25") (pin "2") (pinfunction "2_2") (pintype "passive"))
      (node (ref "D10") (pin "A") (pinfunction "A_A") (pintype "passive"))
      (node (ref "D11") (pin "C") (pinfunction "C_C") (pintype "passive"))
      (node (ref "D12") (pin "A") (pinfunction "A_A") (pintype "passive"))
      (node (ref "D8") (pin "A") (pinfunction "A_A") (pintype "passive"))
      (node (ref "D9") (pin "A") (pinfunction "A_A") (pintype "passive"))
      (node (ref "JP4") (pin "P$2") (pinfunction "2_P$2") (pintype "passive"))
      (node (ref "R28") (pin "1") (pinfunction "1_1") (pintype "passive"))
      (node (ref "R29") (pin "1") (pinfunction "1_1") (pintype "passive"))
      (node (ref "R30") (pin "2") (pinfunction "2_2") (pintype "passive"))
      (node (ref "R31") (pin "2") (pinfunction "2_2") (pintype "passive"))
      (node (ref "U$7") (pin "P$1") (pinfunction "-IN_P$1") (pintype "bidirectional"))
      (node (ref "U$8") (pin "P$1") (pinfunction "-IN_P$1") (pintype "bidirectional"))
      (node (ref "V-") (pin "P$1") (pinfunction "1_P$1") (pintype "passive"))
    )
    (net (code "53") (name "/VBUS") (class "Default")
      (node (ref "433") (pin "2") (pinfunction "2_2") (pintype "passive"))
      (node (ref "C24") (pin "1") (pinfunction "1_1") (pintype "passive"))
      (node (ref "C26") (pin "1") (pinfunction "1_1") (pintype "passive"))
      (node (ref "C3") (pin "2") (pinfunction "2_2") (pintype "passive"))
      (node (ref "C4") (pin "2") (pinfunction "2_2") (pintype "passive"))
      (node (ref "D3") (pin "A") (pinfunction "A_A") (pintype "passive"))
      (node (ref "IC1") (pin "16") (pinfunction "VCC_16") (pintype "power_in"))
      (node (ref "S1") (pin "3") (pinfunction "S_3") (pintype "passive"))
      (node (ref "SJ13") (pin "3") (pinfunction "3_3") (pintype "passive"))
      (node (ref "SJ4") (pin "2") (pinfunction "2_2") (pintype "passive"))
      (node (ref "SJ8") (pin "3") (pinfunction "3_3") (pintype "passive"))
      (node (ref "U$9") (pin "16") (pinfunction "VCC_16") (pintype "bidirectional"))
      (node (ref "U3") (pin "7") (pinfunction "REGIN_7") (pintype "passive"))
      (node (ref "U3") (pin "8") (pinfunction "VBUS_8") (pintype "input"))
    )
    (net (code "54") (name "3.3V") (class "Default")
      (node (ref "C11") (pin "1") (pinfunction "1_1") (pintype "passive"))
      (node (ref "C12") (pin "1") (pinfunction "1_1") (pintype "passive"))
      (node (ref "C13") (pin "1") (pinfunction "1_1") (pintype "passive"))
      (node (ref "C14") (pin "1") (pinfunction "1_1") (pintype "passive"))
      (node (ref "C15") (pin "A") (pinfunction "+_A") (pintype "passive"))
      (node (ref "C17") (pin "1") (pinfunction "1_1") (pintype "passive"))
      (node (ref "C18") (pin "1") (pinfunction "1_1") (pintype "passive"))
      (node (ref "C19") (pin "1") (pinfunction "1_1") (pintype "passive"))
      (node (ref "C2") (pin "A") (pinfunction "+_A") (pintype "passive"))
      (node (ref "C23") (pin "1") (pinfunction "1_1") (pintype "passive"))
      (node (ref "C27") (pin "1") (pinfunction "1_1") (pintype "passive"))
      (node (ref "C28") (pin "1") (pinfunction "1_1") (pintype "passive"))
      (node (ref "C6") (pin "2") (pinfunction "2_2") (pintype "passive"))
      (node (ref "D1") (pin "A") (pinfunction "A_A") (pintype "passive"))
      (node (ref "D13") (pin "A") (pinfunction "A_A") (pintype "passive"))
      (node (ref "D14") (pin "A") (pinfunction "A_A") (pintype "passive"))
      (node (ref "D15") (pin "A") (pinfunction "A_A") (pintype "passive"))
      (node (ref "D2") (pin "A") (pinfunction "A_A") (pintype "passive"))
      (node (ref "D4") (pin "2") (pinfunction "C2_2") (pintype "passive"))
      (node (ref "D5") (pin "2") (pinfunction "C2_2") (pintype "passive"))
      (node (ref "D6") (pin "2") (pinfunction "C2_2") (pintype "passive"))
      (node (ref "D7") (pin "2") (pinfunction "C2_2") (pintype "passive"))
      (node (ref "JP5") (pin "2") (pinfunction "2_2") (pintype "bidirectional"))
      (node (ref "L1") (pin "2") (pinfunction "2_2") (pintype "passive"))
      (node (ref "L2") (pin "1") (pinfunction "1_1") (pintype "passive"))
      (node (ref "OLED") (pin "2") (pinfunction "2_2") (pintype "passive"))
      (node (ref "OS1") (pin "4") (pinfunction "VDD_4") (pintype "power_in"))
      (node (ref "R14") (pin "1") (pinfunction "1_1") (pintype "passive"))
      (node (ref "R2") (pin "2") (pinfunction "2_2") (pintype "passive"))
      (node (ref "R24") (pin "2") (pinfunction "2_2") (pintype "passive"))
      (node (ref "R25") (pin "2") (pinfunction "2_2") (pintype "passive"))
      (node (ref "R33") (pin "2") (pinfunction "2_2") (pintype "passive"))
      (node (ref "R34") (pin "2") (pinfunction "2_2") (pintype "passive"))
      (node (ref "R37") (pin "2") (pinfunction "2_2") (pintype "passive"))
      (node (ref "R38") (pin "2") (pinfunction "2_2") (pintype "passive"))
      (node (ref "R39") (pin "2") (pinfunction "2_2") (pintype "passive"))
      (node (ref "R40") (pin "2") (pinfunction "2_2") (pintype "passive"))
      (node (ref "SJ10") (pin "1") (pinfunction "1_1") (pintype "passive"))
      (node (ref "SJ11") (pin "3") (pinfunction "3_3") (pintype "passive"))
      (node (ref "SJ12") (pin "1") (pinfunction "1_1") (pintype "passive"))
      (node (ref "SJ13") (pin "1") (pinfunction "1_1") (pintype "passive"))
      (node (ref "SJ14") (pin "1") (pinfunction "1_1") (pintype "passive"))
      (node (ref "SJ2") (pin "3") (pinfunction "3_3") (pintype "passive"))
      (node (ref "SJ3") (pin "1") (pinfunction "1_1") (pintype "passive"))
      (node (ref "SJ7") (pin "1") (pinfunction "1_1") (pintype "passive"))
      (node (ref "SJ8") (pin "1") (pinfunction "1_1") (pintype "passive"))
      (node (ref "SJ9") (pin "3") (pinfunction "3_3") (pintype "passive"))
      (node (ref "STLINK") (pin "1") (pinfunction "1_1") (pintype "passive"))
      (node (ref "U$3") (pin "4") (pinfunction "SHDN_4") (pintype "bidirectional"))
      (node (ref "U$3") (pin "5") (pinfunction "VIN_5") (pintype "bidirectional"))
      (node (ref "U$4") (pin "7") (pinfunction "VDD_7") (pintype "bidirectional"))
      (node (ref "U$7") (pin "P$6") (pinfunction "V+_P$6") (pintype "bidirectional"))
      (node (ref "U$8") (pin "P$6") (pinfunction "V+_P$6") (pintype "bidirectional"))
      (node (ref "U1") (pin "2") (pinfunction "OUT_2") (pintype "output"))
      (node (ref "U1") (pin "4") (pinfunction "OUT_4") (pintype "output"))
      (node (ref "U4") (pin "24") (pinfunction "VDD_24") (pintype "power_in"))
      (node (ref "U4") (pin "36") (pinfunction "VDD_36") (pintype "power_in"))
      (node (ref "U4") (pin "48") (pinfunction "VDD_48") (pintype "power_in"))
      (node (ref "U5") (pin "8") (pinfunction "VCC_8") (pintype "bidirectional"))
      (node (ref "U6") (pin "8") (pinfunction "VCC_8") (pintype "bidirectional"))
      (node (ref "U7") (pin "8") (pinfunction "VDD_8") (pintype "bidirectional"))
    )
    (net (code "55") (name "5V") (class "Default")
      (node (ref "U2") (pin "4") (pinfunction "VCC_4") (pintype "bidirectional"))
    )
    (net (code "56") (name "15V") (class "Default")
      (node (ref "C20") (pin "1") (pinfunction "1_1") (pintype "passive"))
      (node (ref "MBRM130LT3G") (pin "C") (pinfunction "C_C") (pintype "passive"))
      (node (ref "R17") (pin "2") (pinfunction "2_2") (pintype "passive"))
      (node (ref "U$4") (pin "9") (pinfunction "VCC_C_9") (pintype "bidirectional"))
    )
    (net (code "57") (name "GND") (class "Default")
      (node (ref "433") (pin "1") (pinfunction "1_1") (pintype "passive"))
      (node (ref "C1") (pin "C") (pinfunction "-_C") (pintype "passive"))
      (node (ref "C10") (pin "2") (pinfunction "2_2") (pintype "passive"))
      (node (ref "C11") (pin "2") (pinfunction "2_2") (pintype "passive"))
      (node (ref "C12") (pin "2") (pinfunction "2_2") (pintype "passive"))
      (node (ref "C13") (pin "2") (pinfunction "2_2") (pintype "passive"))
      (node (ref "C14") (pin "2") (pinfunction "2_2") (pintype "passive"))
      (node (ref "C15") (pin "C") (pinfunction "-_C") (pintype "passive"))
      (node (ref "C16") (pin "2") (pinfunction "2_2") (pintype "passive"))
      (node (ref "C17") (pin "2") (pinfunction "2_2") (pintype "passive"))
      (node (ref "C18") (pin "2") (pinfunction "2_2") (pintype "passive"))
      (node (ref "C19") (pin "2") (pinfunction "2_2") (pintype "passive"))
      (node (ref "C2") (pin "C") (pinfunction "-_C") (pintype "passive"))
      (node (ref "C20") (pin "2") (pinfunction "2_2") (pintype "passive"))
      (node (ref "C21") (pin "2") (pinfunction "2_2") (pintype "passive"))
      (node (ref "C22") (pin "2") (pinfunction "2_2") (pintype "passive"))
      (node (ref "C23") (pin "2") (pinfunction "2_2") (pintype "passive"))
      (node (ref "C24") (pin "2") (pinfunction "2_2") (pintype "passive"))
      (node (ref "C26") (pin "2") (pinfunction "2_2") (pintype "passive"))
      (node (ref "C27") (pin "2") (pinfunction "2_2") (pintype "passive"))
      (node (ref "C28") (pin "2") (pinfunction "2_2") (pintype "passive"))
      (node (ref "C3") (pin "1") (pinfunction "1_1") (pintype "passive"))
      (node (ref "C4") (pin "1") (pinfunction "1_1") (pintype "passive"))
      (node (ref "C5") (pin "2") (pinfunction "2_2") (pintype "passive"))
      (node (ref "C6") (pin "1") (pinfunction "1_1") (pintype "passive"))
      (node (ref "C7") (pin "1") (pinfunction "1_1") (pintype "passive"))
      (node (ref "C8") (pin "2") (pinfunction "2_2") (pintype "passive"))
      (node (ref "C9") (pin "2") (pinfunction "2_2") (pintype "passive"))
      (node (ref "D4") (pin "1") (pinfunction "A1_1") (pintype "passive"))
      (node (ref "D5") (pin "1") (pinfunction "A1_1") (pintype "passive"))
      (node (ref "D6") (pin "1") (pinfunction "A1_1") (pintype "passive"))
      (node (ref "D7") (pin "1") (pinfunction "A1_1") (pintype "passive"))
      (node (ref "IC1") (pin "13") (pinfunction "G_13") (pintype "input"))
      (node (ref "IC1") (pin "8") (pinfunction "GND_8") (pintype "power_in"))
      (node (ref "JP5") (pin "1") (pinfunction "1_1") (pintype "bidirectional"))
      (node (ref "JP5") (pin "3") (pinfunction "3_3") (pintype "bidirectional"))
      (node (ref "JP5") (pin "5") (pinfunction "5_5") (pintype "bidirectional"))
      (node (ref "M1") (pin "1") (pinfunction "1_1") (pintype "passive"))
      (node (ref "M2") (pin "1") (pinfunction "1_1") (pintype "passive"))
      (node (ref "OLED") (pin "1") (pinfunction "1_1") (pintype "passive"))
      (node (ref "OS1") (pin "2") (pinfunction "VSS_2") (pintype "power_in"))
      (node (ref "R1") (pin "2") (pinfunction "2_2") (pintype "passive"))
      (node (ref "R13") (pin "2") (pinfunction "2_2") (pintype "passive"))
      (node (ref "R18") (pin "1") (pinfunction "1_1") (pintype "passive"))
      (node (ref "R19") (pin "2") (pinfunction "2_2") (pintype "passive"))
      (node (ref "R20") (pin "6") (pinfunction "2_6") (pintype "passive"))
      (node (ref "R23") (pin "1") (pinfunction "1_1") (pintype "passive"))
      (node (ref "R3") (pin "2") (pinfunction "2_2") (pintype "passive"))
      (node (ref "R36") (pin "1") (pinfunction "1_1") (pintype "passive"))
      (node (ref "R4") (pin "1") (pinfunction "1_1") (pintype "passive"))
      (node (ref "R44") (pin "1") (pinfunction "1_1") (pintype "passive"))
      (node (ref "R45") (pin "1") (pinfunction "1_1") (pintype "passive"))
      (node (ref "R7") (pin "1") (pinfunction "1_1") (pintype "passive"))
      (node (ref "S2") (pin "1") (pinfunction "1_1") (pintype "passive"))
      (node (ref "SJ1") (pin "2") (pinfunction "2_2") (pintype "passive"))
      (node (ref "SJ10") (pin "3") (pinfunction "3_3") (pintype "passive"))
      (node (ref "SJ11") (pin "1") (pinfunction "1_1") (pintype "passive"))
      (node (ref "SJ12") (pin "3") (pinfunction "3_3") (pintype "passive"))
      (node (ref "SJ14") (pin "3") (pinfunction "3_3") (pintype "passive"))
      (node (ref "SJ2") (pin "1") (pinfunction "1_1") (pintype "passive"))
      (node (ref "SJ3") (pin "3") (pinfunction "3_3") (pintype "passive"))
      (node (ref "SJ7") (pin "3") (pinfunction "3_3") (pintype "passive"))
      (node (ref "SJ9") (pin "1") (pinfunction "1_1") (pintype "passive"))
      (node (ref "STLINK") (pin "2") (pinfunction "2_2") (pintype "passive"))
      (node (ref "SW1") (pin "1") (pinfunction "1_1") (pintype "passive"))
      (node (ref "SW1") (pin "2") (pinfunction "2_2") (pintype "passive"))
      (node (ref "SW1") (pin "3") (pinfunction "3_3") (pintype "passive"))
      (node (ref "SW1") (pin "4") (pinfunction "4_4") (pintype "passive"))
      (node (ref "SW1") (pin "5") (pinfunction "5_5") (pintype "passive"))
      (node (ref "SW1") (pin "6") (pinfunction "6_6") (pintype "passive"))
      (node (ref "SW1") (pin "7") (pinfunction "7_7") (pintype "passive"))
      (node (ref "SW1") (pin "8") (pinfunction "8_8") (pintype "passive"))
      (node (ref "U$3") (pin "2") (pinfunction "GND_2") (pintype "bidirectional"))
      (node (ref "U$4") (pin "11") (pinfunction "VSS_11") (pintype "bidirectional"))
      (node (ref "U$7") (pin "P$2") (pinfunction "GND_P$2") (pintype "bidirectional"))
      (node (ref "U$8") (pin "P$2") (pinfunction "GND_P$2") (pintype "bidirectional"))
      (node (ref "U$9") (pin "7") (pinfunction "OE_7") (pintype "bidirectional"))
      (node (ref "U$9") (pin "8") (pinfunction "GND_8") (pintype "bidirectional"))
      (node (ref "U1") (pin "1") (pinfunction "ADJ_1") (pintype "input"))
      (node (ref "U2") (pin "1") (pinfunction "GND_1") (pintype "bidirectional"))
      (node (ref "U3") (pin "3") (pinfunction "GND_3") (pintype "power_in"))
      (node (ref "U3") (pin "EXP") (pinfunction "GND_EXP") (pintype "power_in"))
      (node (ref "U3") (pin "M") (pinfunction "GND_M") (pintype "power_in"))
      (node (ref "U4") (pin "23") (pinfunction "VSS_23") (pintype "power_in"))
      (node (ref "U4") (pin "35") (pinfunction "VSS_35") (pintype "power_in"))
      (node (ref "U4") (pin "47") (pinfunction "VSS_47") (pintype "power_in"))
      (node (ref "U4") (pin "8") (pinfunction "VSSA_8") (pintype "power_in"))
      (node (ref "U5") (pin "5") (pinfunction "GND_5") (pintype "bidirectional"))
      (node (ref "U6") (pin "5") (pinfunction "GND_5") (pintype "bidirectional"))
      (node (ref "U7") (pin "3") (pinfunction "VSS_3") (pintype "bidirectional"))
      (node (ref "U8") (pin "C") (pinfunction "C_C") (pintype "bidirectional"))
      (node (ref "USART") (pin "3") (pinfunction "3_3") (pintype "passive"))
    )
    (net (code "58") (name "Net-(C1-+)") (class "Default")
      (node (ref "C1") (pin "A") (pinfunction "+_A") (pintype "passive"))
      (node (ref "C16") (pin "1") (pinfunction "1_1") (pintype "passive"))
      (node (ref "D3") (pin "C") (pinfunction "C_C") (pintype "passive"))
      (node (ref "U1") (pin "3") (pinfunction "IN_3") (pintype "input"))
    )
    (net (code "59") (name "Net-(D1-PadC)") (class "Default")
      (node (ref "D1") (pin "C") (pinfunction "C_C") (pintype "passive"))
      (node (ref "R4") (pin "2") (pinfunction "2_2") (pintype "passive"))
    )
    (net (code "60") (name "Net-(D4-C1A2)") (class "Default")
      (node (ref "D4") (pin "3") (pinfunction "C1A2_3") (pintype "passive"))
      (node (ref "R35") (pin "1") (pinfunction "1_1") (pintype "passive"))
      (node (ref "R36") (pin "2") (pinfunction "2_2") (pintype "passive"))
      (node (ref "U7") (pin "6") (pinfunction "AIN2_6") (pintype "bidirectional"))
    )
    (net (code "61") (name "Net-(D5-C1A2)") (class "Default")
      (node (ref "D5") (pin "3") (pinfunction "C1A2_3") (pintype "passive"))
      (node (ref "R43") (pin "1") (pinfunction "1_1") (pintype "passive"))
      (node (ref "R44") (pin "2") (pinfunction "2_2") (pintype "passive"))
      (node (ref "U7") (pin "5") (pinfunction "AIN1_5") (pintype "bidirectional"))
    )
    (net (code "62") (name "Net-(D6-C1A2)") (class "Default")
      (node (ref "D6") (pin "3") (pinfunction "C1A2_3") (pintype "passive"))
      (node (ref "R45") (pin "2") (pinfunction "2_2") (pintype "passive"))
      (node (ref "R46") (pin "1") (pinfunction "1_1") (pintype "passive"))
      (node (ref "U7") (pin "4") (pinfunction "AIN0_4") (pintype "bidirectional"))
    )
    (net (code "63") (name "Net-(D7-C1A2)") (class "Default")
      (node (ref "D7") (pin "3") (pinfunction "C1A2_3") (pintype "passive"))
      (node (ref "R22") (pin "1") (pinfunction "1_1") (pintype "passive"))
      (node (ref "R23") (pin "2") (pinfunction "2_2") (pintype "passive"))
      (node (ref "U7") (pin "7") (pinfunction "AIN3_7") (pintype "bidirectional"))
    )
    (net (code "64") (name "Net-(D11-PadA)") (class "Default")
      (node (ref "D11") (pin "A") (pinfunction "A_A") (pintype "passive"))
      (node (ref "D12") (pin "C") (pinfunction "C_C") (pintype "passive"))
      (node (ref "R32") (pin "2") (pinfunction "2_2") (pintype "passive"))
    )
    (net (code "65") (name "Net-(IC1A-QF)") (class "Default")
      (node (ref "IC1") (pin "5") (pinfunction "QF_5") (pintype "tri_state"))
      (node (ref "R7") (pin "4") (pinfunction "1_4") (pintype "passive"))
    )
    (net (code "66") (name "Net-(IC1A-QG)") (class "Default")
      (node (ref "IC1") (pin "6") (pinfunction "QG_6") (pintype "tri_state"))
      (node (ref "R7") (pin "3") (pinfunction "1_3") (pintype "passive"))
    )
    (net (code "67") (name "Net-(IC1A-QH)") (class "Default")
      (node (ref "IC1") (pin "7") (pinfunction "QH_7") (pintype "tri_state"))
      (node (ref "R7") (pin "2") (pinfunction "1_2") (pintype "passive"))
    )
    (net (code "68") (name "Net-(JP1-PadGND)") (class "Default")
      (node (ref "JP1") (pin "GND") (pinfunction "GND_GND") (pintype "bidirectional"))
      (node (ref "R1") (pin "1") (pinfunction "1_1") (pintype "passive"))
    )
    (net (code "69") (name "Net-(M1-Pad2)") (class "Default")
      (node (ref "M1") (pin "2") (pinfunction "2_2") (pintype "passive"))
      (node (ref "R35") (pin "2") (pinfunction "2_2") (pintype "passive"))
    )
    (net (code "70") (name "Net-(M1-Pad3)") (class "Default")
      (node (ref "M1") (pin "3") (pinfunction "3_3") (pintype "passive"))
      (node (ref "SJ13") (pin "2") (pinfunction "2_2") (pintype "passive"))
    )
    (net (code "71") (name "Net-(M2-Pad2)") (class "Default")
      (node (ref "M2") (pin "2") (pinfunction "2_2") (pintype "passive"))
      (node (ref "R22") (pin "2") (pinfunction "2_2") (pintype "passive"))
    )
    (net (code "72") (name "Net-(M2-Pad3)") (class "Default")
      (node (ref "M2") (pin "3") (pinfunction "3_3") (pintype "passive"))
      (node (ref "SJ8") (pin "2") (pinfunction "2_2") (pintype "passive"))
    )
    (net (code "73") (name "Net-(OS1-CON)") (class "Default")
      (node (ref "OS1") (pin "1") (pinfunction "CON_1") (pintype "input"))
      (node (ref "SJ2") (pin "2") (pinfunction "2_2") (pintype "passive"))
    )
    (net (code "74") (name "Net-(R5-Pad2)") (class "Default")
      (node (ref "R5") (pin "2") (pinfunction "2_2") (pintype "passive"))
      (node (ref "SJ14") (pin "2") (pinfunction "2_2") (pintype "passive"))
    )
    (net (code "75") (name "Net-(R6-Pad1)") (class "Default")
      (node (ref "R6") (pin "1") (pinfunction "1_1") (pintype "passive"))
      (node (ref "SJ3") (pin "2") (pinfunction "2_2") (pintype "passive"))
    )
    (net (code "76") (name "Net-(R7A-2)") (class "Default")
      (node (ref "R7") (pin "8") (pinfunction "2_8") (pintype "passive"))
      (node (ref "S3") (pin "3") (pinfunction "2_3") (pintype "passive"))
    )
    (net (code "77") (name "Net-(R7B-2)") (class "Default")
      (node (ref "D13") (pin "C") (pinfunction "C_C") (pintype "passive"))
      (node (ref "R7") (pin "7") (pinfunction "2_7") (pintype "passive"))
    )
    (net (code "78") (name "Net-(R7C-2)") (class "Default")
      (node (ref "D15") (pin "C") (pinfunction "C_C") (pintype "passive"))
      (node (ref "R7") (pin "5") (pinfunction "2_5") (pintype "passive"))
    )
    (net (code "79") (name "Net-(R7D-2)") (class "Default")
      (node (ref "D14") (pin "C") (pinfunction "C_C") (pintype "passive"))
      (node (ref "R7") (pin "6") (pinfunction "2_6") (pintype "passive"))
    )
    (net (code "80") (name "Net-(R16-Pad1)") (class "Default")
      (node (ref "R16") (pin "1") (pinfunction "1_1") (pintype "passive"))
      (node (ref "SJ6") (pin "2") (pinfunction "2_2") (pintype "passive"))
    )
    (net (code "81") (name "Net-(R16A-2)") (class "Default")
      (node (ref "R16") (pin "8") (pinfunction "2_8") (pintype "passive"))
      (node (ref "U6") (pin "1") (pinfunction "RO_1") (pintype "bidirectional"))
    )
    (net (code "82") (name "Net-(R16B-2)") (class "Default")
      (node (ref "R16") (pin "7") (pinfunction "2_7") (pintype "passive"))
      (node (ref "U6") (pin "2") (pinfunction "RE_2") (pintype "bidirectional"))
    )
    (net (code "83") (name "Net-(R16C-1)") (class "Default")
      (node (ref "R16") (pin "4") (pinfunction "1_4") (pintype "passive"))
      (node (ref "SJ5") (pin "2") (pinfunction "2_2") (pintype "passive"))
    )
    (net (code "84") (name "Net-(R16C-2)") (class "Default")
      (node (ref "R16") (pin "5") (pinfunction "2_5") (pintype "passive"))
      (node (ref "U6") (pin "4") (pinfunction "DI_4") (pintype "bidirectional"))
    )
    (net (code "85") (name "Net-(R16D-2)") (class "Default")
      (node (ref "R16") (pin "6") (pinfunction "2_6") (pintype "passive"))
      (node (ref "U6") (pin "3") (pinfunction "SHDN_3") (pintype "bidirectional"))
    )
    (net (code "86") (name "Net-(S1-P)") (class "Default")
      (node (ref "JP1") (pin "VBUS") (pinfunction "VBUS_VBUS") (pintype "bidirectional"))
      (node (ref "S1") (pin "2") (pinfunction "P_2") (pintype "passive"))
      (node (ref "SJ4") (pin "1") (pinfunction "1_1") (pintype "passive"))
    )
    (net (code "87") (name "Net-(U$3-FB)") (class "Default")
      (node (ref "R17") (pin "1") (pinfunction "1_1") (pintype "passive"))
      (node (ref "R18") (pin "2") (pinfunction "2_2") (pintype "passive"))
      (node (ref "U$3") (pin "3") (pinfunction "FB_3") (pintype "bidirectional"))
    )
    (net (code "88") (name "Net-(U$3-SW)") (class "Default")
      (node (ref "L2") (pin "2") (pinfunction "2_2") (pintype "passive"))
      (node (ref "MBRM130LT3G") (pin "A") (pinfunction "A_A") (pintype "passive"))
      (node (ref "U$3") (pin "1") (pinfunction "SW_1") (pintype "bidirectional"))
    )
    (net (code "89") (name "Net-(U$4-IREF)") (class "Default")
      (node (ref "R19") (pin "1") (pinfunction "1_1") (pintype "passive"))
      (node (ref "U$4") (pin "8") (pinfunction "IREF_8") (pintype "bidirectional"))
    )
    (net (code "90") (name "Net-(U$4-IXS)") (class "Default")
      (node (ref "SJ7") (pin "2") (pinfunction "2_2") (pintype "passive"))
      (node (ref "U$4") (pin "1") (pinfunction "IXS_1") (pintype "bidirectional"))
    )
    (net (code "91") (name "Net-(U$4-VCC_R)") (class "Default")
      (node (ref "C21") (pin "1") (pinfunction "1_1") (pintype "passive"))
      (node (ref "C22") (pin "1") (pinfunction "1_1") (pintype "passive"))
      (node (ref "U$4") (pin "10") (pinfunction "VCC_R_10") (pintype "bidirectional"))
    )
    (net (code "92") (name "Net-(U$5-P$1)") (class "Default")
      (node (ref "R24") (pin "1") (pinfunction "1_1") (pintype "passive"))
      (node (ref "U$5") (pin "1") (pinfunction "P$1_1") (pintype "bidirectional"))
    )
    (net (code "93") (name "Net-(U$5-P$3)") (class "Default")
      (node (ref "R28") (pin "2") (pinfunction "2_2") (pintype "passive"))
      (node (ref "U$5") (pin "3") (pinfunction "P$3_3") (pintype "bidirectional"))
    )
    (net (code "94") (name "Net-(U$6-P$1)") (class "Default")
      (node (ref "R25") (pin "1") (pinfunction "1_1") (pintype "passive"))
      (node (ref "U$6") (pin "1") (pinfunction "P$1_1") (pintype "bidirectional"))
    )
    (net (code "95") (name "Net-(U$6-P$3)") (class "Default")
      (node (ref "R29") (pin "2") (pinfunction "2_2") (pintype "passive"))
      (node (ref "U$6") (pin "3") (pinfunction "P$3_3") (pintype "bidirectional"))
    )
    (net (code "96") (name "Net-(U$7-+IN)") (class "Default")
      (node (ref "R31") (pin "1") (pinfunction "1_1") (pintype "passive"))
      (node (ref "SERVO2") (pin "1") (pinfunction "1_1") (pintype "passive"))
      (node (ref "U$7") (pin "P$8") (pinfunction "+IN_P$8") (pintype "bidirectional"))
    )
    (net (code "97") (name "Net-(U$7-REF1)") (class "Default")
      (node (ref "SJ10") (pin "2") (pinfunction "2_2") (pintype "passive"))
      (node (ref "U$7") (pin "P$7") (pinfunction "REF1_P$7") (pintype "bidirectional"))
    )
    (net (code "98") (name "Net-(U$7-REF2)") (class "Default")
      (node (ref "SJ9") (pin "2") (pinfunction "2_2") (pintype "passive"))
      (node (ref "U$7") (pin "P$3") (pinfunction "REF2_P$3") (pintype "bidirectional"))
    )
    (net (code "99") (name "Net-(U$8-+IN)") (class "Default")
      (node (ref "R30") (pin "1") (pinfunction "1_1") (pintype "passive"))
      (node (ref "SERVO1") (pin "1") (pinfunction "1_1") (pintype "passive"))
      (node (ref "U$8") (pin "P$8") (pinfunction "+IN_P$8") (pintype "bidirectional"))
    )
    (net (code "100") (name "Net-(U$8-REF1)") (class "Default")
      (node (ref "SJ12") (pin "2") (pinfunction "2_2") (pintype "passive"))
      (node (ref "U$8") (pin "P$7") (pinfunction "REF1_P$7") (pintype "bidirectional"))
    )
    (net (code "101") (name "Net-(U$8-REF2)") (class "Default")
      (node (ref "SJ11") (pin "2") (pinfunction "2_2") (pintype "passive"))
      (node (ref "U$8") (pin "P$3") (pinfunction "REF2_P$3") (pintype "bidirectional"))
    )
    (net (code "102") (name "Net-(U$9-B5)") (class "Default")
      (node (ref "SW1") (pin "13") (pinfunction "13_13") (pintype "passive"))
      (node (ref "U$9") (pin "15") (pinfunction "B5_15") (pintype "bidirectional"))
    )
    (net (code "103") (name "Net-(U$9-B6)") (class "Default")
      (node (ref "SW1") (pin "14") (pinfunction "14_14") (pintype "passive"))
      (node (ref "U$9") (pin "14") (pinfunction "B6_14") (pintype "bidirectional"))
    )
    (net (code "104") (name "Net-(U$9-B7)") (class "Default")
      (node (ref "SW1") (pin "15") (pinfunction "15_15") (pintype "passive"))
      (node (ref "U$9") (pin "13") (pinfunction "B7_13") (pintype "bidirectional"))
    )
    (net (code "105") (name "Net-(U$9-B8)") (class "Default")
      (node (ref "SW1") (pin "16") (pinfunction "16_16") (pintype "passive"))
      (node (ref "U$9") (pin "12") (pinfunction "B8_12") (pintype "bidirectional"))
    )
    (net (code "106") (name "Net-(U3-VDD)") (class "Default")
      (node (ref "C5") (pin "1") (pinfunction "1_1") (pintype "passive"))
      (node (ref "U3") (pin "6") (pinfunction "VDD_6") (pintype "power_in"))
    )
    (net (code "107") (name "Net-(U3-~{RST})") (class "Default")
      (node (ref "R2") (pin "1") (pinfunction "1_1") (pintype "passive"))
      (node (ref "SJ1") (pin "1") (pinfunction "1_1") (pintype "passive"))
      (node (ref "U3") (pin "9") (pinfunction "~{RST}_9") (pintype "bidirectional"))
    )
    (net (code "108") (name "Net-(U3-~{SUSPEND})") (class "Default")
      (node (ref "R3") (pin "1") (pinfunction "1_1") (pintype "passive"))
      (node (ref "U3") (pin "11") (pinfunction "~{SUSPEND}_11") (pintype "output"))
    )
    (net (code "109") (name "Net-(U4A-BOOT0)") (class "Default")
      (node (ref "R6") (pin "2") (pinfunction "2_2") (pintype "passive"))
      (node (ref "U4") (pin "44") (pinfunction "BOOT0_44") (pintype "input"))
    )
    (net (code "110") (name "Net-(U4A-PB2)") (class "Default")
      (node (ref "R5") (pin "1") (pinfunction "1_1") (pintype "passive"))
      (node (ref "U4") (pin "20") (pinfunction "PB2_20") (pintype "bidirectional"))
    )
    (net (code "111") (name "Net-(U4A-VBAT)") (class "Default")
      (node (ref "D2") (pin "C") (pinfunction "C_C") (pintype "passive"))
      (node (ref "U4") (pin "1") (pinfunction "VBAT_1") (pintype "power_in"))
    )
    (net (code "112") (name "Net-(U4A-VDDA)") (class "Default")
      (node (ref "C10") (pin "1") (pinfunction "1_1") (pintype "passive"))
      (node (ref "C8") (pin "1") (pinfunction "1_1") (pintype "passive"))
      (node (ref "C9") (pin "1") (pinfunction "1_1") (pintype "passive"))
      (node (ref "L1") (pin "1") (pinfunction "1_1") (pintype "passive"))
      (node (ref "U4") (pin "9") (pinfunction "VDDA_9") (pintype "power_in"))
    )
    (net (code "113") (name "unconnected-(433-Pad7)") (class "Default")
      (node (ref "433") (pin "7") (pinfunction "7_7") (pintype "passive"))
    )
    (net (code "114") (name "unconnected-(IC1A-QH*-Pad9)") (class "Default")
      (node (ref "IC1") (pin "9") (pinfunction "QH*_9") (pintype "tri_state"))
    )
    (net (code "115") (name "unconnected-(R20C-1-Pad4)") (class "Default")
      (node (ref "R20") (pin "4") (pinfunction "1_4") (pintype "passive"))
    )
    (net (code "116") (name "unconnected-(R20C-2-Pad5)") (class "Default")
      (node (ref "R20") (pin "5") (pinfunction "2_5") (pintype "passive"))
    )
    (net (code "117") (name "unconnected-(S1-O-Pad1)") (class "Default")
      (node (ref "S1") (pin "1") (pinfunction "O_1") (pintype "passive"))
    )
    (net (code "118") (name "unconnected-(U3-CTS-Pad23)") (class "Default")
      (node (ref "U3") (pin "23") (pinfunction "CTS_23") (pintype "input"))
    )
    (net (code "119") (name "unconnected-(U3-DCD-Pad1)") (class "Default")
      (node (ref "U3") (pin "1") (pinfunction "DCD_1") (pintype "input"))
    )
    (net (code "120") (name "unconnected-(U3-DSR-Pad27)") (class "Default")
      (node (ref "U3") (pin "27") (pinfunction "DSR_27") (pintype "input"))
    )
    (net (code "121") (name "unconnected-(U3-DTR-Pad28)") (class "Default")
      (node (ref "U3") (pin "28") (pinfunction "DTR_28") (pintype "output"))
    )
    (net (code "122") (name "unconnected-(U3-RI-Pad2)") (class "Default")
      (node (ref "U3") (pin "2") (pinfunction "RI_2") (pintype "input"))
    )
    (net (code "123") (name "unconnected-(U3-RTS-Pad24)") (class "Default")
      (node (ref "U3") (pin "24") (pinfunction "RTS_24") (pintype "output"))
    )
    (net (code "124") (name "unconnected-(U3-SUSPEND-Pad12)") (class "Default")
      (node (ref "U3") (pin "12") (pinfunction "SUSPEND_12") (pintype "output"))
    )
    (net (code "125") (name "unconnected-(U4A-OSC_OUT-Pad6)") (class "Default")
      (node (ref "U4") (pin "6") (pinfunction "OSC_OUT_6") (pintype "bidirectional"))
    )
    (net (code "126") (name "unconnected-(U4A-PA4-Pad14)") (class "Default")
      (node (ref "U4") (pin "14") (pinfunction "PA4_14") (pintype "bidirectional"))
    )
    (net (code "127") (name "unconnected-(U4A-PA12-Pad33)") (class "Default")
      (node (ref "U4") (pin "33") (pinfunction "PA12_33") (pintype "bidirectional"))
    )
    (net (code "128") (name "unconnected-(U4A-PC13-Pad2)") (class "Default")
      (node (ref "U4") (pin "2") (pinfunction "PC13_2") (pintype "bidirectional"))
    )
    (net (code "129") (name "unconnected-(U4A-PC14-Pad3)") (class "Default")
      (node (ref "U4") (pin "3") (pinfunction "PC14_3") (pintype "bidirectional"))
    )
    (net (code "130") (name "unconnected-(U4A-PC15-Pad4)") (class "Default")
      (node (ref "U4") (pin "4") (pinfunction "PC15_4") (pintype "bidirectional"))
    )
  )
)
